# Simple-Charger-LiIon-OpampBased-LM358.net
KiCad netlist of a schematic drawn in EAGLE
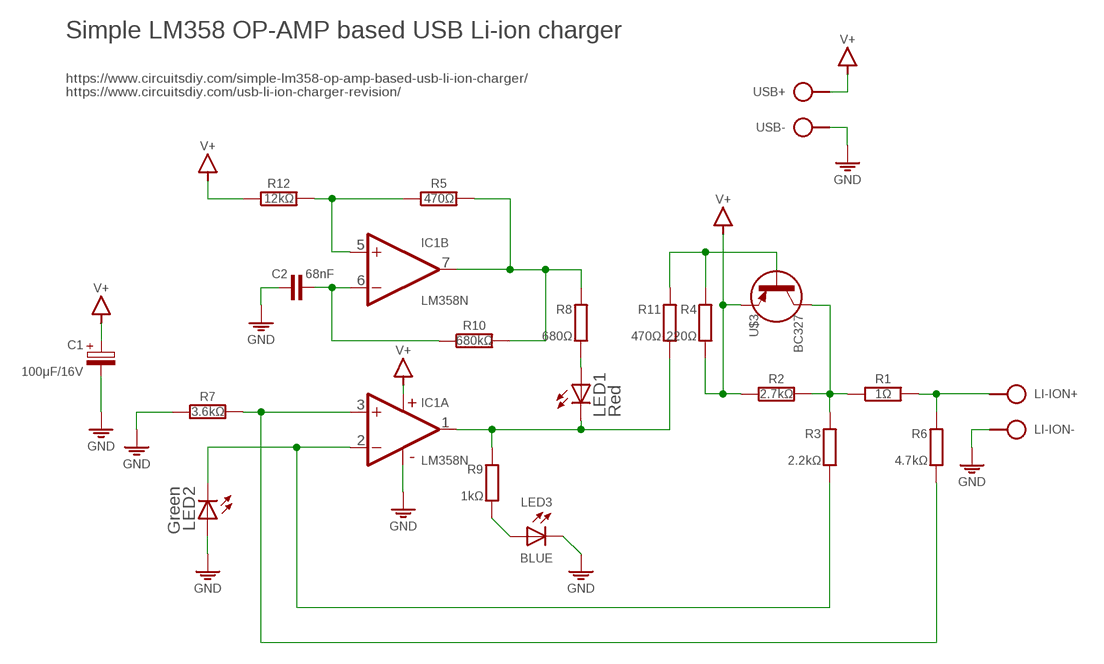
[diagram p0: schematic, sheet 1]

(export (version "E")
  (design (tool "Eeschema 10.0.6"))
  (components
    (comp (ref "C1")
      (value "100μF/16V")
      (footprint "eagle-import:E2,5-5")
      (libsource (lib "eagle-import") (part "CPOLE2.5-5"))
    )
    (comp (ref "C2")
      (value "68nF")
      (footprint "eagle-import:C075-020X044_V")
      (libsource (lib "eagle-import") (part "C-H075-020X044/V"))
    )
    (comp (ref "IC1")
      (value "LM358N")
      (footprint "eagle-import:DIL08")
      (libsource (lib "eagle-import") (part "LM358N"))
    )
    (comp (ref "LED1")
      (value "Red")
      (footprint "eagle-import:LED3MM")
      (libsource (lib "eagle-import") (part "LED3MM"))
    )
    (comp (ref "LED2")
      (value "Green")
      (footprint "eagle-import:LED3MM")
      (libsource (lib "eagle-import") (part "LED3MM"))
    )
    (comp (ref "LED3")
      (value "BLUE")
      (footprint "eagle-import:LED_3MM")
      (libsource (lib "eagle-import") (part "LED-H-3MM"))
    )
    (comp (ref "LI-ION")
      (value "SPAD+-+-")
      (footprint "eagle-import:SPAD+-")
      (libsource (lib "eagle-import") (part "SPAD+-+-"))
    )
    (comp (ref "R1")
      (value "1Ω")
      (footprint "eagle-import:0204_10-V")
      (libsource (lib "eagle-import") (part "R-H0204/10-V"))
    )
    (comp (ref "R2")
      (value "2.7kΩ")
      (footprint "eagle-import:0204_10-V")
      (libsource (lib "eagle-import") (part "R-H0204/10-V"))
    )
    (comp (ref "R3")
      (value "2.2kΩ")
      (footprint "eagle-import:0204_10-V")
      (libsource (lib "eagle-import") (part "R0204/10-V"))
    )
    (comp (ref "R4")
      (value "220Ω")
      (footprint "eagle-import:0204_10-V")
      (libsource (lib "eagle-import") (part "R0204/10-V"))
    )
    (comp (ref "R5")
      (value "470Ω")
      (footprint "eagle-import:0204_7-V")
      (libsource (lib "eagle-import") (part "R-H0204/7-V"))
    )
    (comp (ref "R6")
      (value "4.7kΩ")
      (footprint "eagle-import:0204_10-V")
      (libsource (lib "eagle-import") (part "R0204/10-V"))
    )
    (comp (ref "R7")
      (value "3.6kΩ")
      (footprint "eagle-import:0204_10")
      (libsource (lib "eagle-import") (part "R-H0204/10"))
    )
    (comp (ref "R8")
      (value "680Ω")
      (footprint "eagle-import:0204_10-V")
      (libsource (lib "eagle-import") (part "R0204/10-V"))
    )
    (comp (ref "R9")
      (value "1kΩ")
      (footprint "eagle-import:0204_10")
      (libsource (lib "eagle-import") (part "R0204/10"))
    )
    (comp (ref "R10")
      (value "680kΩ")
      (footprint "eagle-import:0204_10-V")
      (libsource (lib "eagle-import") (part "R-H0204/10-V"))
    )
    (comp (ref "R11")
      (value "470Ω")
      (footprint "eagle-import:0204_10-V")
      (libsource (lib "eagle-import") (part "R0204/10-V"))
    )
    (comp (ref "R12")
      (value "12kΩ")
      (footprint "eagle-import:0204_10-V")
      (libsource (lib "eagle-import") (part "R-H0204/10-V"))
    )
    (comp (ref "U$3")
      (value "BC327")
      (footprint "eagle-import:TO92")
      (libsource (lib "eagle-import") (part "BC327"))
    )
    (comp (ref "USB")
      (value "SPAD+--+")
      (footprint "eagle-import:SPAD-+")
      (libsource (lib "eagle-import") (part "SPAD+--+"))
    )
  )
  (nets
    (net (code "1") (name "GND") (class "Default")
      (node (ref "C1") (pin "-") (pinfunction "-_-") (pintype "passive"))
      (node (ref "C2") (pin "1") (pinfunction "1_1") (pintype "passive"))
      (node (ref "IC1") (pin "4") (pinfunction "V-_4") (pintype "power_in"))
      (node (ref "LED2") (pin "A") (pinfunction "A_A") (pintype "passive"))
      (node (ref "LED3") (pin "K") (pinfunction "K_K") (pintype "passive"))
      (node (ref "LI-ION") (pin "1") (pinfunction "P$1_1") (pintype "passive"))
      (node (ref "R7") (pin "1") (pinfunction "1_1") (pintype "passive"))
      (node (ref "USB") (pin "1") (pinfunction "P$1_1") (pintype "passive"))
    )
    (net (code "2") (name "Net-(IC1A-+IN)") (class "Default")
      (node (ref "IC1") (pin "3") (pinfunction "+IN_3") (pintype "input"))
      (node (ref "R6") (pin "2") (pinfunction "2_2") (pintype "passive"))
      (node (ref "R7") (pin "2") (pinfunction "2_2") (pintype "passive"))
    )
    (net (code "3") (name "Net-(IC1A--IN)") (class "Default")
      (node (ref "IC1") (pin "2") (pinfunction "-IN_2") (pintype "input"))
      (node (ref "LED2") (pin "K") (pinfunction "C_K") (pintype "passive"))
      (node (ref "R3") (pin "2") (pinfunction "2_2") (pintype "passive"))
    )
    (net (code "4") (name "Net-(IC1A-OUT)") (class "Default")
      (node (ref "IC1") (pin "1") (pinfunction "OUT_1") (pintype "output"))
      (node (ref "LED1") (pin "K") (pinfunction "C_K") (pintype "passive"))
      (node (ref "R11") (pin "2") (pinfunction "2_2") (pintype "passive"))
      (node (ref "R9") (pin "1") (pinfunction "1_1") (pintype "passive"))
    )
    (net (code "5") (name "Net-(IC1B-+IN)") (class "Default")
      (node (ref "IC1") (pin "5") (pinfunction "+IN_5") (pintype "input"))
      (node (ref "R12") (pin "2") (pinfunction "2_2") (pintype "passive"))
      (node (ref "R5") (pin "1") (pinfunction "1_1") (pintype "passive"))
    )
    (net (code "6") (name "Net-(IC1B--IN)") (class "Default")
      (node (ref "C2") (pin "2") (pinfunction "2_2") (pintype "passive"))
      (node (ref "IC1") (pin "6") (pinfunction "-IN_6") (pintype "input"))
      (node (ref "R10") (pin "1") (pinfunction "1_1") (pintype "passive"))
    )
    (net (code "7") (name "Net-(IC1B-OUT)") (class "Default")
      (node (ref "IC1") (pin "7") (pinfunction "OUT_7") (pintype "output"))
      (node (ref "R10") (pin "2") (pinfunction "2_2") (pintype "passive"))
      (node (ref "R5") (pin "2") (pinfunction "2_2") (pintype "passive"))
      (node (ref "R8") (pin "1") (pinfunction "1_1") (pintype "passive"))
    )
    (net (code "8") (name "Net-(LED1-PadA)") (class "Default")
      (node (ref "LED1") (pin "A") (pinfunction "A_A") (pintype "passive"))
      (node (ref "R8") (pin "2") (pinfunction "2_2") (pintype "passive"))
    )
    (net (code "9") (name "Net-(LED3-PadA)") (class "Default")
      (node (ref "LED3") (pin "A") (pinfunction "A_A") (pintype "passive"))
      (node (ref "R9") (pin "2") (pinfunction "2_2") (pintype "passive"))
    )
    (net (code "10") (name "Net-(LI-IONA-P$1)") (class "Default")
      (node (ref "LI-ION") (pin "2") (pinfunction "P$1_2") (pintype "passive"))
      (node (ref "R1") (pin "2") (pinfunction "2_2") (pintype "passive"))
      (node (ref "R6") (pin "1") (pinfunction "1_1") (pintype "passive"))
    )
    (net (code "11") (name "Net-(U$3-B)") (class "Default")
      (node (ref "R11") (pin "1") (pinfunction "1_1") (pintype "passive"))
      (node (ref "R4") (pin "1") (pinfunction "1_1") (pintype "passive"))
      (node (ref "U$3") (pin "2") (pinfunction "B_2") (pintype "passive"))
    )
    (net (code "12") (name "Net-(U$3-C)") (class "Default")
      (node (ref "R1") (pin "1") (pinfunction "1_1") (pintype "passive"))
      (node (ref "R2") (pin "2") (pinfunction "2_2") (pintype "passive"))
      (node (ref "R3") (pin "1") (pinfunction "1_1") (pintype "passive"))
      (node (ref "U$3") (pin "1") (pinfunction "C_1") (pintype "passive"))
    )
    (net (code "13") (name "V+") (class "Default")
      (node (ref "C1") (pin "+") (pinfunction "+_+") (pintype "passive"))
      (node (ref "IC1") (pin "8") (pinfunction "V+_8") (pintype "power_in"))
      (node (ref "R12") (pin "1") (pinfunction "1_1") (pintype "passive"))
      (node (ref "R2") (pin "1") (pinfunction "1_1") (pintype "passive"))
      (node (ref "R4") (pin "2") (pinfunction "2_2") (pintype "passive"))
      (node (ref "U$3") (pin "3") (pinfunction "E_3") (pintype "passive"))
      (node (ref "USB") (pin "2") (pinfunction "P$1_2") (pintype "passive"))
    )
  )
)
